# USB.net
KiCad netlist of a schematic drawn in Altium Designer
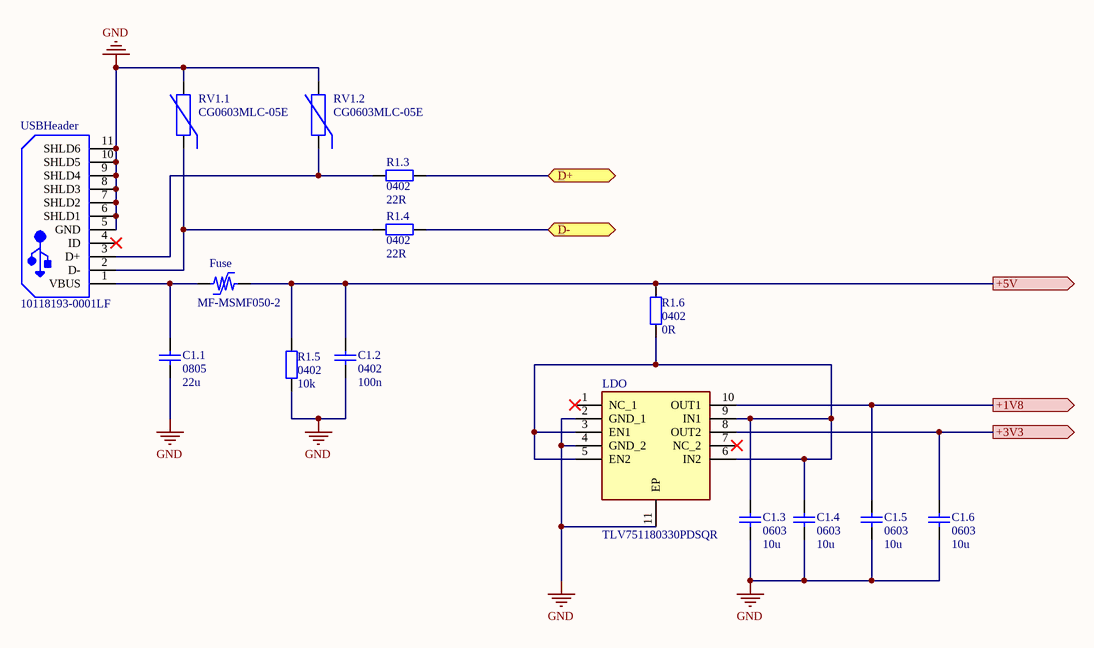
[diagram p0: USB.SchDoc]

(export (version "E")
  (design (tool "Eeschema 10.0.6"))
  (components
    (comp (ref "C1.1")
      (value "0805")
      (footprint "C0805_M")
      (description "Capacitor")
      (fields
        (field (name "PART NUMBER") "C0805_X5R_22u_20%")
        (field (name "ALTIUM_VALUE") "22u")
        (field (name "TOLERANCE") "20%")
      )
      (libsource (lib "LTE_altium") (part "Cap"))
    )
    (comp (ref "C1.2")
      (value "0402")
      (footprint "C0402_M")
      (description "Capacitor")
      (fields
        (field (name "PART NUMBER") "C0402_X7R_100n_10%")
        (field (name "ALTIUM_VALUE") "100n")
        (field (name "TOLERANCE") "10%")
      )
      (libsource (lib "LTE_altium") (part "Cap"))
    )
    (comp (ref "C1.3")
      (value "0603")
      (footprint "C0603_M")
      (description "Capacitor")
      (fields
        (field (name "PART NUMBER") "C0603_X5R_10u_10%")
        (field (name "ALTIUM_VALUE") "10u")
        (field (name "TOLERANCE") "10%")
      )
      (libsource (lib "LTE_altium") (part "Cap"))
    )
    (comp (ref "C1.4")
      (value "0603")
      (footprint "C0603_M")
      (description "Capacitor")
      (fields
        (field (name "PART NUMBER") "C0603_X5R_10u_10%")
        (field (name "ALTIUM_VALUE") "10u")
        (field (name "TOLERANCE") "10%")
      )
      (libsource (lib "LTE_altium") (part "Cap"))
    )
    (comp (ref "C1.5")
      (value "0603")
      (footprint "C0603_M")
      (description "Capacitor")
      (fields
        (field (name "PART NUMBER") "C0603_X5R_10u_10%")
        (field (name "ALTIUM_VALUE") "10u")
        (field (name "TOLERANCE") "10%")
      )
      (libsource (lib "LTE_altium") (part "Cap"))
    )
    (comp (ref "C1.6")
      (value "0603")
      (footprint "C0603_M")
      (description "Capacitor")
      (fields
        (field (name "PART NUMBER") "C0603_X5R_10u_10%")
        (field (name "ALTIUM_VALUE") "10u")
        (field (name "TOLERANCE") "10%")
      )
      (libsource (lib "LTE_altium") (part "Cap"))
    )
    (comp (ref "Fuse")
      (value "MF-MSMF050-2")
      (footprint "BOUR-MF-MSMF050-2_V")
      (description "PTC Resettable Fuse, 15 V, 500 mA, -40 to 85 degC, 2-Pin SMD, RoHS, Tape and Reel")
      (fields (field (name "MANUFACTURER") "Bourns"))
      (libsource (lib "Altium Content Vault") (part "PPTC-2"))
    )
    (comp (ref "LDO")
      (value "TLV751180330PDSQR")
      (footprint "SON40P200X200X80-11N")
      (description "Integrated Circuit")
      (fields (field (name "MOUSER PART NUMBER") "595-LV751180330PDSQR"))
      (libsource (lib "SamacSys") (part "TLV751180330PDSQR"))
    )
    (comp (ref "R1.3")
      (value "0402")
      (footprint "R0402_M")
      (description "Resistor")
      (fields
        (field (name "PART NUMBER") "R0402_1%_220R")
        (field (name "ALTIUM_VALUE") "22R")
        (field (name "TOLERANCE") "1%")
      )
      (libsource (lib "LTE_altium") (part "Res"))
    )
    (comp (ref "R1.4")
      (value "0402")
      (footprint "R0402_M")
      (description "Resistor")
      (fields
        (field (name "PART NUMBER") "R0402_1%_220R")
        (field (name "ALTIUM_VALUE") "22R")
        (field (name "TOLERANCE") "1%")
      )
      (libsource (lib "LTE_altium") (part "Res"))
    )
    (comp (ref "R1.5")
      (value "0402")
      (footprint "R0402_M")
      (description "Resistor")
      (fields
        (field (name "PART NUMBER") "R0402_1%_10k")
        (field (name "ALTIUM_VALUE") "10k")
        (field (name "TOLERANCE") "1%")
      )
      (libsource (lib "") (part "Res_1"))
    )
    (comp (ref "R1.6")
      (value "0402")
      (footprint "R0402_M")
      (description "Resistor")
      (fields
        (field (name "PART NUMBER") "R0402_1%_0R")
        (field (name "ALTIUM_VALUE") "0R")
        (field (name "TOLERANCE") "1%")
      )
      (libsource (lib "") (part "Res_1"))
    )
    (comp (ref "RV1.1")
      (value "CG0603MLC-05E")
      (footprint "BOUR-CG0603-2_V")
      (description "ESD Protector, 5 V Supply, -40 to 85 degC, 1.6 x 0.8 x 0.55 mm SMD, RoHS, Tape and Reel")
      (fields (field (name "MANUFACTURER") "Bourns"))
      (libsource (lib "Altium Content Vault") (part "BOUR-VSR-2"))
    )
    (comp (ref "RV1.2")
      (value "CG0603MLC-05E")
      (footprint "BOUR-CG0603-2_V")
      (description "ESD Protector, 5 V Supply, -40 to 85 degC, 1.6 x 0.8 x 0.55 mm SMD, RoHS, Tape and Reel")
      (fields (field (name "MANUFACTURER") "Bourns"))
      (libsource (lib "Altium Content Vault") (part "BOUR-VSR-2"))
    )
    (comp (ref "USBHeader")
      (value "10118193-0001LF")
      (footprint "FCI-10118193-0001LF-5_V")
      (description "Micro USB B Type Receptacle, -55 to 85 degC, 5-Pin SMD, RoHS, Tape and Reel")
      (fields (field (name "MANUFACTURER") "FCI"))
      (libsource (lib "Altium Content Vault") (part "USB-5-6SHLD"))
    )
  )
  (nets
    (net (code "1") (name "/+1V8") (class "Default")
      (node (ref "C1.5") (pin "2") (pinfunction "2_2") (pintype "passive"))
      (node (ref "LDO") (pin "10") (pinfunction "OUT1_10") (pintype "passive"))
    )
    (net (code "2") (name "/+3V3") (class "Default")
      (node (ref "C1.6") (pin "2") (pinfunction "2_2") (pintype "passive"))
      (node (ref "LDO") (pin "8") (pinfunction "OUT2_8") (pintype "passive"))
    )
    (net (code "3") (name "/+5V") (class "Default")
      (node (ref "C1.2") (pin "2") (pinfunction "2_2") (pintype "passive"))
      (node (ref "Fuse") (pin "2") (pinfunction "2_2") (pintype "passive"))
      (node (ref "R1.5") (pin "2") (pinfunction "2_2") (pintype "passive"))
      (node (ref "R1.6") (pin "2") (pinfunction "2_2") (pintype "passive"))
    )
    (net (code "4") (name "/D+") (class "Default")
      (node (ref "R1.3") (pin "2") (pinfunction "2_2") (pintype "passive"))
    )
    (net (code "5") (name "/D-") (class "Default")
      (node (ref "R1.4") (pin "2") (pinfunction "2_2") (pintype "passive"))
    )
    (net (code "6") (name "GND") (class "Default")
      (node (ref "C1.1") (pin "1") (pinfunction "1_1") (pintype "passive"))
      (node (ref "C1.2") (pin "1") (pinfunction "1_1") (pintype "passive"))
      (node (ref "C1.3") (pin "1") (pinfunction "1_1") (pintype "passive"))
      (node (ref "C1.4") (pin "1") (pinfunction "1_1") (pintype "passive"))
      (node (ref "C1.5") (pin "1") (pinfunction "1_1") (pintype "passive"))
      (node (ref "C1.6") (pin "1") (pinfunction "1_1") (pintype "passive"))
      (node (ref "LDO") (pin "11") (pinfunction "EP_11") (pintype "passive"))
      (node (ref "LDO") (pin "2") (pinfunction "GND_1_2") (pintype "passive"))
      (node (ref "LDO") (pin "4") (pinfunction "GND_2_4") (pintype "passive"))
      (node (ref "R1.5") (pin "1") (pinfunction "1_1") (pintype "passive"))
      (node (ref "RV1.1") (pin "2") (pinfunction "2_2") (pintype "passive"))
      (node (ref "RV1.2") (pin "2") (pinfunction "2_2") (pintype "passive"))
      (node (ref "USBHeader") (pin "10") (pinfunction "SHLD5_10") (pintype "passive"))
      (node (ref "USBHeader") (pin "11") (pinfunction "SHLD6_11") (pintype "passive"))
      (node (ref "USBHeader") (pin "5") (pinfunction "GND_5") (pintype "passive"))
      (node (ref "USBHeader") (pin "6") (pinfunction "SHLD1_6") (pintype "passive"))
      (node (ref "USBHeader") (pin "7") (pinfunction "SHLD2_7") (pintype "passive"))
      (node (ref "USBHeader") (pin "8") (pinfunction "SHLD3_8") (pintype "passive"))
      (node (ref "USBHeader") (pin "9") (pinfunction "SHLD4_9") (pintype "passive"))
    )
    (net (code "7") (name "Net-(LDO-EN1)") (class "Default")
      (node (ref "C1.3") (pin "2") (pinfunction "2_2") (pintype "passive"))
      (node (ref "C1.4") (pin "2") (pinfunction "2_2") (pintype "passive"))
      (node (ref "LDO") (pin "3") (pinfunction "EN1_3") (pintype "passive"))
      (node (ref "LDO") (pin "5") (pinfunction "EN2_5") (pintype "passive"))
      (node (ref "LDO") (pin "6") (pinfunction "IN2_6") (pintype "passive"))
      (node (ref "LDO") (pin "9") (pinfunction "IN1_9") (pintype "passive"))
      (node (ref "R1.6") (pin "1") (pinfunction "1_1") (pintype "passive"))
    )
    (net (code "8") (name "Net-(USBHeader-D+)") (class "Default")
      (node (ref "R1.3") (pin "1") (pinfunction "1_1") (pintype "passive"))
      (node (ref "RV1.2") (pin "1") (pinfunction "1_1") (pintype "passive"))
      (node (ref "USBHeader") (pin "3") (pinfunction "D+_3") (pintype "passive"))
    )
    (net (code "9") (name "Net-(USBHeader-D-)") (class "Default")
      (node (ref "R1.4") (pin "1") (pinfunction "1_1") (pintype "passive"))
      (node (ref "RV1.1") (pin "1") (pinfunction "1_1") (pintype "passive"))
      (node (ref "USBHeader") (pin "2") (pinfunction "D-_2") (pintype "passive"))
    )
    (net (code "10") (name "Net-(USBHeader-VBUS)") (class "Default")
      (node (ref "C1.1") (pin "2") (pinfunction "2_2") (pintype "passive"))
      (node (ref "Fuse") (pin "1") (pinfunction "1_1") (pintype "passive"))
      (node (ref "USBHeader") (pin "1") (pinfunction "VBUS_1") (pintype "passive"))
    )
    (net (code "11") (name "unconnected-(LDO-NC_1-Pad1)") (class "Default")
      (node (ref "LDO") (pin "1") (pinfunction "NC_1_1") (pintype "passive+no_connect"))
    )
    (net (code "12") (name "unconnected-(LDO-NC_2-Pad7)") (class "Default")
      (node (ref "LDO") (pin "7") (pinfunction "NC_2_7") (pintype "passive+no_connect"))
    )
    (net (code "13") (name "unconnected-(USBHeader-ID-Pad4)") (class "Default")
      (node (ref "USBHeader") (pin "4") (pinfunction "ID_4") (pintype "passive+no_connect"))
    )
  )
)
